# 6WP.net
KiCad netlist of a schematic drawn in EAGLE
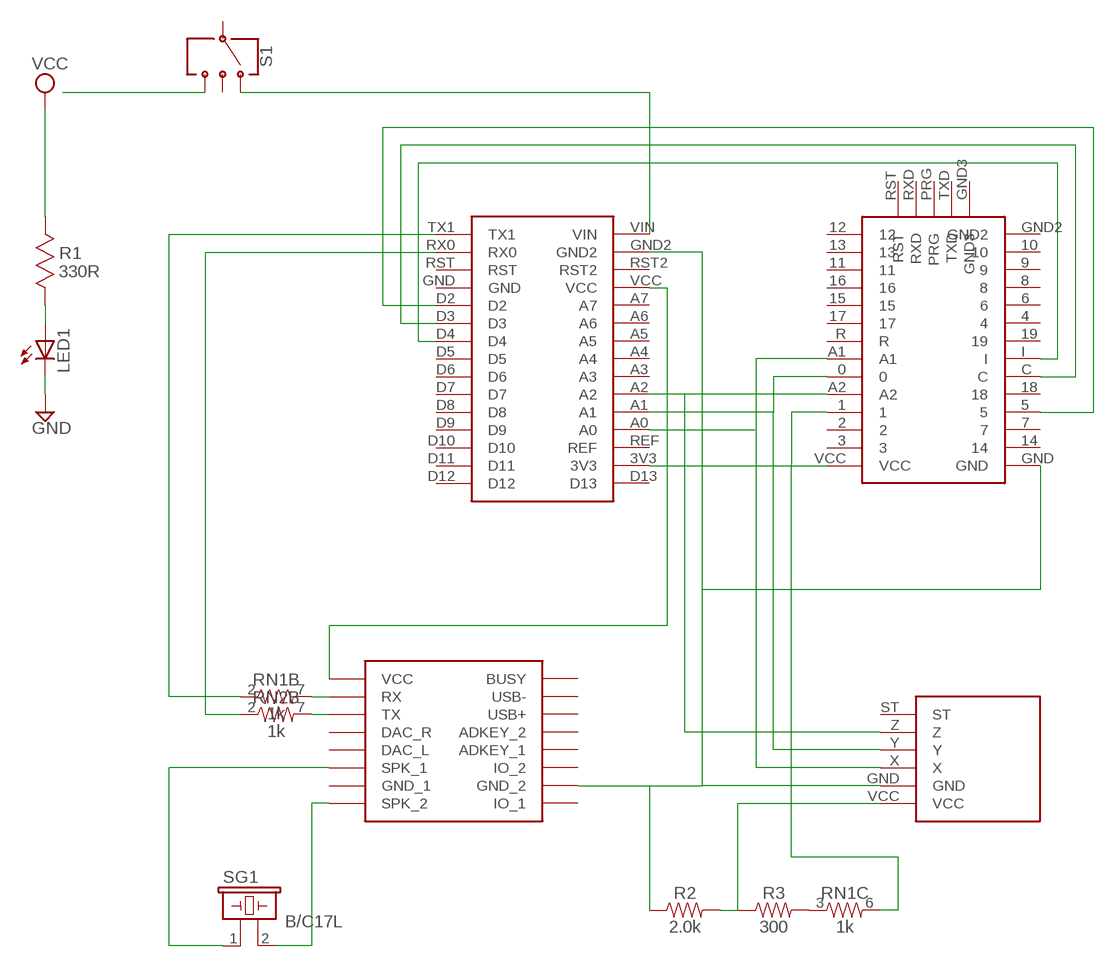
[diagram p0: schematic, sheet 1]

(export (version "E")
  (design (tool "Eeschema 10.0.6"))
  (components
    (comp (ref "A1")
      (value "ARDUINONANO")
      (footprint "eagle-import:ARDUINONANO")
      (libsource (lib "eagle-import") (part "ARDUINONANO"))
    )
    (comp (ref "A2")
      (value "TWELITEDIP")
      (footprint "eagle-import:TWELITEDIP")
      (libsource (lib "eagle-import") (part "TWELITEDIP"))
    )
    (comp (ref "A3")
      (value "ADXL335")
      (footprint "eagle-import:ADXL335")
      (libsource (lib "eagle-import") (part "ADXL335"))
    )
    (comp (ref "LED1")
      (value "LEDCHIP-LED0603")
      (footprint "eagle-import:CHIP-LED0603")
      (libsource (lib "eagle-import") (part "LEDCHIP-LED0603"))
    )
    (comp (ref "R1")
      (value "330R")
      (footprint "eagle-import:RESC1608X60N")
      (fields (field (name "MPN") "MC0.063W06031%330R") (field (name "TOLERANCE") "±1%"))
      (libsource (lib "eagle-import") (part "MC0.063W06031%330R"))
    )
    (comp (ref "R2")
      (value "2.0k")
      (footprint "eagle-import:0603")
      (libsource (lib "eagle-import") (part "2.0KOHM-0603-1/10W-5%"))
    )
    (comp (ref "R3")
      (value "300")
      (footprint "eagle-import:0603")
      (libsource (lib "eagle-import") (part "300OHM-0603-1/10W-1%"))
    )
    (comp (ref "RN1")
      (value "1k")
      (footprint "eagle-import:0805-ARV")
      (libsource (lib "eagle-import") (part "1KOHM-ARRAY(4)-0805_ARV-1/10W-5%"))
    )
    (comp (ref "RN2")
      (value "1k")
      (footprint "eagle-import:0805-ARV")
      (libsource (lib "eagle-import") (part "1KOHM-ARRAY(4)-0805_ARV-1/10W-5%"))
    )
    (comp (ref "S1")
      (value "SWITCH-SP3T-SMD")
      (footprint "eagle-import:SWITCH_SP3T_SMD")
      (libsource (lib "eagle-import") (part "SWITCH-SP3T-SMD"))
    )
    (comp (ref "SG1")
      (value "B/C17L")
      (footprint "eagle-import:B_C17L")
      (libsource (lib "eagle-import") (part "B/C17L"))
    )
    (comp (ref "U$2")
      (value "DFPLAYER")
      (footprint "eagle-import:DFPLAYER")
      (libsource (lib "eagle-import") (part "DFPLAYER"))
    )
  )
  (nets
    (net (code "1") (name "GND") (class "Default")
      (node (ref "LED1") (pin "C") (pinfunction "C_C") (pintype "passive"))
    )
    (net (code "2") (name "Net-(A1-PadA0)") (class "Default")
      (node (ref "A1") (pin "A0") (pinfunction "A0_A0") (pintype "bidirectional"))
      (node (ref "A2") (pin "A1") (pinfunction "A1_A1") (pintype "bidirectional"))
      (node (ref "A3") (pin "X") (pinfunction "X_X") (pintype "bidirectional"))
    )
    (net (code "3") (name "Net-(A1-PadA1)") (class "Default")
      (node (ref "A1") (pin "A1") (pinfunction "A1_A1") (pintype "bidirectional"))
      (node (ref "A2") (pin "0") (pinfunction "0_0") (pintype "bidirectional"))
      (node (ref "A3") (pin "Y") (pinfunction "Y_Y") (pintype "bidirectional"))
    )
    (net (code "4") (name "Net-(A1-PadA2)") (class "Default")
      (node (ref "A1") (pin "A2") (pinfunction "A2_A2") (pintype "bidirectional"))
      (node (ref "A2") (pin "A2") (pinfunction "A2_A2") (pintype "bidirectional"))
      (node (ref "A3") (pin "Z") (pinfunction "Z_Z") (pintype "bidirectional"))
    )
    (net (code "5") (name "Net-(A1-PadD2)") (class "Default")
      (node (ref "A1") (pin "D2") (pinfunction "D2_D2") (pintype "bidirectional"))
      (node (ref "A2") (pin "5") (pinfunction "5_5") (pintype "bidirectional"))
    )
    (net (code "6") (name "Net-(A1-PadD3)") (class "Default")
      (node (ref "A1") (pin "D3") (pinfunction "D3_D3") (pintype "bidirectional"))
      (node (ref "A2") (pin "C") (pinfunction "C_C") (pintype "bidirectional"))
    )
    (net (code "7") (name "Net-(A1-PadD4)") (class "Default")
      (node (ref "A1") (pin "D4") (pinfunction "D4_D4") (pintype "bidirectional"))
      (node (ref "A2") (pin "I") (pinfunction "I_I") (pintype "bidirectional"))
    )
    (net (code "8") (name "Net-(A1-PadGND2)") (class "Default")
      (node (ref "A1") (pin "GND2") (pinfunction "GND2_GND2") (pintype "bidirectional"))
      (node (ref "A2") (pin "GND") (pinfunction "GND_GND") (pintype "bidirectional"))
      (node (ref "A3") (pin "GND") (pinfunction "GND_GND") (pintype "bidirectional"))
      (node (ref "R2") (pin "1") (pinfunction "1_1") (pintype "passive"))
      (node (ref "U$2") (pin "GND_2") (pinfunction "GND_2_GND_2") (pintype "bidirectional"))
    )
    (net (code "9") (name "Net-(A1-PadVCC)") (class "Default")
      (node (ref "A1") (pin "VCC") (pinfunction "VCC_VCC") (pintype "bidirectional"))
      (node (ref "U$2") (pin "VCC") (pinfunction "VCC_VCC") (pintype "bidirectional"))
    )
    (net (code "10") (name "Net-(A1-PadVIN)") (class "Default")
      (node (ref "A1") (pin "VIN") (pinfunction "VIN_VIN") (pintype "bidirectional"))
      (node (ref "S1") (pin "1") (pinfunction "1_1") (pintype "bidirectional"))
    )
    (net (code "11") (name "Net-(A3-PadVCC)") (class "Default")
      (node (ref "A3") (pin "VCC") (pinfunction "VCC_VCC") (pintype "bidirectional"))
      (node (ref "R2") (pin "2") (pinfunction "2_2") (pintype "passive"))
      (node (ref "R3") (pin "1") (pinfunction "1_1") (pintype "passive"))
    )
    (net (code "12") (name "Net-(R1-R2)") (class "Default")
      (node (ref "LED1") (pin "A") (pinfunction "A_A") (pintype "passive"))
      (node (ref "R1") (pin "2") (pinfunction "R2_2") (pintype "passive"))
    )
    (net (code "13") (name "Net-(RN1B-1)") (class "Default")
      (node (ref "A1") (pin "TX1") (pinfunction "TX1_TX1") (pintype "bidirectional"))
      (node (ref "RN1") (pin "2") (pinfunction "1_2") (pintype "passive"))
    )
    (net (code "14") (name "Net-(RN1B-2)") (class "Default")
      (node (ref "RN1") (pin "7") (pinfunction "2_7") (pintype "passive"))
      (node (ref "U$2") (pin "RX") (pinfunction "RX_RX") (pintype "bidirectional"))
    )
    (net (code "15") (name "Net-(RN1C-1)") (class "Default")
      (node (ref "R3") (pin "2") (pinfunction "2_2") (pintype "passive"))
      (node (ref "RN1") (pin "3") (pinfunction "1_3") (pintype "passive"))
    )
    (net (code "16") (name "Net-(RN1C-2)") (class "Default")
      (node (ref "A1") (pin "3V3") (pinfunction "3V3_3V3") (pintype "bidirectional"))
      (node (ref "A2") (pin "1") (pinfunction "1_1") (pintype "bidirectional"))
      (node (ref "A2") (pin "VCC") (pinfunction "VCC_VCC") (pintype "bidirectional"))
      (node (ref "RN1") (pin "6") (pinfunction "2_6") (pintype "passive"))
    )
    (net (code "17") (name "Net-(RN2B-1)") (class "Default")
      (node (ref "A1") (pin "RX0") (pinfunction "RX0_RX0") (pintype "bidirectional"))
      (node (ref "RN2") (pin "2") (pinfunction "1_2") (pintype "passive"))
    )
    (net (code "18") (name "Net-(RN2B-2)") (class "Default")
      (node (ref "RN2") (pin "7") (pinfunction "2_7") (pintype "passive"))
      (node (ref "U$2") (pin "TX") (pinfunction "TX_TX") (pintype "bidirectional"))
    )
    (net (code "19") (name "Net-(U$2-SPK_1)") (class "Default")
      (node (ref "SG1") (pin "1") (pinfunction "1_1") (pintype "passive"))
      (node (ref "U$2") (pin "SPK1") (pinfunction "SPK_1_SPK1") (pintype "bidirectional"))
    )
    (net (code "20") (name "Net-(U$2-SPK_2)") (class "Default")
      (node (ref "SG1") (pin "2") (pinfunction "2_2") (pintype "passive"))
      (node (ref "U$2") (pin "SPK2") (pinfunction "SPK_2_SPK2") (pintype "bidirectional"))
    )
    (net (code "21") (name "VCC") (class "Default")
      (node (ref "R1") (pin "1") (pinfunction "R1_1") (pintype "passive"))
    )
    (net (code "22") (name "unconnected-(A1-PadA3)") (class "Default")
      (node (ref "A1") (pin "A3") (pinfunction "A3_A3") (pintype "bidirectional"))
    )
    (net (code "23") (name "unconnected-(A1-PadA4)") (class "Default")
      (node (ref "A1") (pin "A4") (pinfunction "A4_A4") (pintype "bidirectional"))
    )
    (net (code "24") (name "unconnected-(A1-PadA5)") (class "Default")
      (node (ref "A1") (pin "A5") (pinfunction "A5_A5") (pintype "bidirectional"))
    )
    (net (code "25") (name "unconnected-(A1-PadA6)") (class "Default")
      (node (ref "A1") (pin "A6") (pinfunction "A6_A6") (pintype "bidirectional"))
    )
    (net (code "26") (name "unconnected-(A1-PadA7)") (class "Default")
      (node (ref "A1") (pin "A7") (pinfunction "A7_A7") (pintype "bidirectional"))
    )
    (net (code "27") (name "unconnected-(A1-PadD5)") (class "Default")
      (node (ref "A1") (pin "D5") (pinfunction "D5_D5") (pintype "bidirectional"))
    )
    (net (code "28") (name "unconnected-(A1-PadD6)") (class "Default")
      (node (ref "A1") (pin "D6") (pinfunction "D6_D6") (pintype "bidirectional"))
    )
    (net (code "29") (name "unconnected-(A1-PadD7)") (class "Default")
      (node (ref "A1") (pin "D7") (pinfunction "D7_D7") (pintype "bidirectional"))
    )
    (net (code "30") (name "unconnected-(A1-PadD8)") (class "Default")
      (node (ref "A1") (pin "D8") (pinfunction "D8_D8") (pintype "bidirectional"))
    )
    (net (code "31") (name "unconnected-(A1-PadD9)") (class "Default")
      (node (ref "A1") (pin "D9") (pinfunction "D9_D9") (pintype "bidirectional"))
    )
    (net (code "32") (name "unconnected-(A1-PadD10)") (class "Default")
      (node (ref "A1") (pin "D10") (pinfunction "D10_D10") (pintype "bidirectional"))
    )
    (net (code "33") (name "unconnected-(A1-PadD11)") (class "Default")
      (node (ref "A1") (pin "D11") (pinfunction "D11_D11") (pintype "bidirectional"))
    )
    (net (code "34") (name "unconnected-(A1-PadD12)") (class "Default")
      (node (ref "A1") (pin "D12") (pinfunction "D12_D12") (pintype "bidirectional"))
    )
    (net (code "35") (name "unconnected-(A1-PadD13)") (class "Default")
      (node (ref "A1") (pin "D13") (pinfunction "D13_D13") (pintype "bidirectional"))
    )
    (net (code "36") (name "unconnected-(A1-PadGND)") (class "Default")
      (node (ref "A1") (pin "GND") (pinfunction "GND_GND") (pintype "bidirectional"))
    )
    (net (code "37") (name "unconnected-(A1-PadREF)") (class "Default")
      (node (ref "A1") (pin "REF") (pinfunction "REF_REF") (pintype "bidirectional"))
    )
    (net (code "38") (name "unconnected-(A1-PadRST)") (class "Default")
      (node (ref "A1") (pin "RST") (pinfunction "RST_RST") (pintype "bidirectional"))
    )
    (net (code "39") (name "unconnected-(A1-PadRST2)") (class "Default")
      (node (ref "A1") (pin "RST2") (pinfunction "RST2_RST2") (pintype "bidirectional"))
    )
    (net (code "40") (name "unconnected-(A2-Pad2)") (class "Default")
      (node (ref "A2") (pin "2") (pinfunction "2_2") (pintype "bidirectional"))
    )
    (net (code "41") (name "unconnected-(A2-Pad3)") (class "Default")
      (node (ref "A2") (pin "3") (pinfunction "3_3") (pintype "bidirectional"))
    )
    (net (code "42") (name "unconnected-(A2-Pad4)") (class "Default")
      (node (ref "A2") (pin "4") (pinfunction "4_4") (pintype "bidirectional"))
    )
    (net (code "43") (name "unconnected-(A2-Pad6)") (class "Default")
      (node (ref "A2") (pin "6") (pinfunction "6_6") (pintype "bidirectional"))
    )
    (net (code "44") (name "unconnected-(A2-Pad7)") (class "Default")
      (node (ref "A2") (pin "7") (pinfunction "7_7") (pintype "bidirectional"))
    )
    (net (code "45") (name "unconnected-(A2-Pad8)") (class "Default")
      (node (ref "A2") (pin "8") (pinfunction "8_8") (pintype "bidirectional"))
    )
    (net (code "46") (name "unconnected-(A2-Pad9)") (class "Default")
      (node (ref "A2") (pin "9") (pinfunction "9_9") (pintype "bidirectional"))
    )
    (net (code "47") (name "unconnected-(A2-Pad10)") (class "Default")
      (node (ref "A2") (pin "10") (pinfunction "10_10") (pintype "bidirectional"))
    )
    (net (code "48") (name "unconnected-(A2-Pad11)") (class "Default")
      (node (ref "A2") (pin "11") (pinfunction "11_11") (pintype "bidirectional"))
    )
    (net (code "49") (name "unconnected-(A2-Pad12)") (class "Default")
      (node (ref "A2") (pin "12") (pinfunction "12_12") (pintype "bidirectional"))
    )
    (net (code "50") (name "unconnected-(A2-Pad13)") (class "Default")
      (node (ref "A2") (pin "13") (pinfunction "13_13") (pintype "bidirectional"))
    )
    (net (code "51") (name "unconnected-(A2-Pad14)") (class "Default")
      (node (ref "A2") (pin "14") (pinfunction "14_14") (pintype "bidirectional"))
    )
    (net (code "52") (name "unconnected-(A2-Pad15)") (class "Default")
      (node (ref "A2") (pin "15") (pinfunction "15_15") (pintype "bidirectional"))
    )
    (net (code "53") (name "unconnected-(A2-Pad16)") (class "Default")
      (node (ref "A2") (pin "16") (pinfunction "16_16") (pintype "bidirectional"))
    )
    (net (code "54") (name "unconnected-(A2-Pad17)") (class "Default")
      (node (ref "A2") (pin "17") (pinfunction "17_17") (pintype "bidirectional"))
    )
    (net (code "55") (name "unconnected-(A2-Pad18)") (class "Default")
      (node (ref "A2") (pin "18") (pinfunction "18_18") (pintype "bidirectional"))
    )
    (net (code "56") (name "unconnected-(A2-Pad19)") (class "Default")
      (node (ref "A2") (pin "19") (pinfunction "19_19") (pintype "bidirectional"))
    )
    (net (code "57") (name "unconnected-(A2-PadGND2)") (class "Default")
      (node (ref "A2") (pin "GND2") (pinfunction "GND2_GND2") (pintype "bidirectional"))
    )
    (net (code "58") (name "unconnected-(A2-PadGND3)") (class "Default")
      (node (ref "A2") (pin "GND3") (pinfunction "GND3_GND3") (pintype "bidirectional"))
    )
    (net (code "59") (name "unconnected-(A2-PadPRG)") (class "Default")
      (node (ref "A2") (pin "PRG") (pinfunction "PRG_PRG") (pintype "bidirectional"))
    )
    (net (code "60") (name "unconnected-(A2-PadR)") (class "Default")
      (node (ref "A2") (pin "R") (pinfunction "R_R") (pintype "bidirectional"))
    )
    (net (code "61") (name "unconnected-(A2-PadRST)") (class "Default")
      (node (ref "A2") (pin "RST") (pinfunction "RST_RST") (pintype "bidirectional"))
    )
    (net (code "62") (name "unconnected-(A2-PadRXD)") (class "Default")
      (node (ref "A2") (pin "RXD") (pinfunction "RXD_RXD") (pintype "bidirectional"))
    )
    (net (code "63") (name "unconnected-(A2-PadTXD)") (class "Default")
      (node (ref "A2") (pin "TXD") (pinfunction "TXD_TXD") (pintype "bidirectional"))
    )
    (net (code "64") (name "unconnected-(A3-PadST)") (class "Default")
      (node (ref "A3") (pin "ST") (pinfunction "ST_ST") (pintype "bidirectional"))
    )
    (net (code "65") (name "unconnected-(S1-Pad2)") (class "Default")
      (node (ref "S1") (pin "2") (pinfunction "2_2") (pintype "bidirectional"))
    )
    (net (code "66") (name "unconnected-(S1-Pad3)") (class "Default")
      (node (ref "S1") (pin "3") (pinfunction "3_3") (pintype "bidirectional"))
    )
    (net (code "67") (name "unconnected-(S1-Pad4)") (class "Default")
      (node (ref "S1") (pin "4") (pinfunction "4_4") (pintype "bidirectional"))
    )
    (net (code "68") (name "unconnected-(U$2-ADKEY_1-PadADKEY1)") (class "Default")
      (node (ref "U$2") (pin "ADKEY1") (pinfunction "ADKEY_1_ADKEY1") (pintype "bidirectional"))
    )
    (net (code "69") (name "unconnected-(U$2-ADKEY_2-PadADKEY2)") (class "Default")
      (node (ref "U$2") (pin "ADKEY2") (pinfunction "ADKEY_2_ADKEY2") (pintype "bidirectional"))
    )
    (net (code "70") (name "unconnected-(U$2-IO_1-PadIO1)") (class "Default")
      (node (ref "U$2") (pin "IO1") (pinfunction "IO_1_IO1") (pintype "bidirectional"))
    )
    (net (code "71") (name "unconnected-(U$2-IO_2-PadIO2)") (class "Default")
      (node (ref "U$2") (pin "IO2") (pinfunction "IO_2_IO2") (pintype "bidirectional"))
    )
    (net (code "72") (name "unconnected-(U$2-PadBUSY)") (class "Default")
      (node (ref "U$2") (pin "BUSY") (pinfunction "BUSY_BUSY") (pintype "bidirectional"))
    )
    (net (code "73") (name "unconnected-(U$2-PadDAC_L)") (class "Default")
      (node (ref "U$2") (pin "DAC_L") (pinfunction "DAC_L_DAC_L") (pintype "bidirectional"))
    )
    (net (code "74") (name "unconnected-(U$2-PadDAC_R)") (class "Default")
      (node (ref "U$2") (pin "DAC_R") (pinfunction "DAC_R_DAC_R") (pintype "bidirectional"))
    )
    (net (code "75") (name "unconnected-(U$2-PadGND_1)") (class "Default")
      (node (ref "U$2") (pin "GND_1") (pinfunction "GND_1_GND_1") (pintype "bidirectional"))
    )
    (net (code "76") (name "unconnected-(U$2-PadUSB+)") (class "Default")
      (node (ref "U$2") (pin "USB+") (pinfunction "USB+_USB+") (pintype "bidirectional"))
    )
    (net (code "77") (name "unconnected-(U$2-PadUSB-)") (class "Default")
      (node (ref "U$2") (pin "USB-") (pinfunction "USB-_USB-") (pintype "bidirectional"))
    )
  )
)
